# Pmaster-A9112-HOST_0.net
KiCad netlist of a schematic drawn in Altium Designer
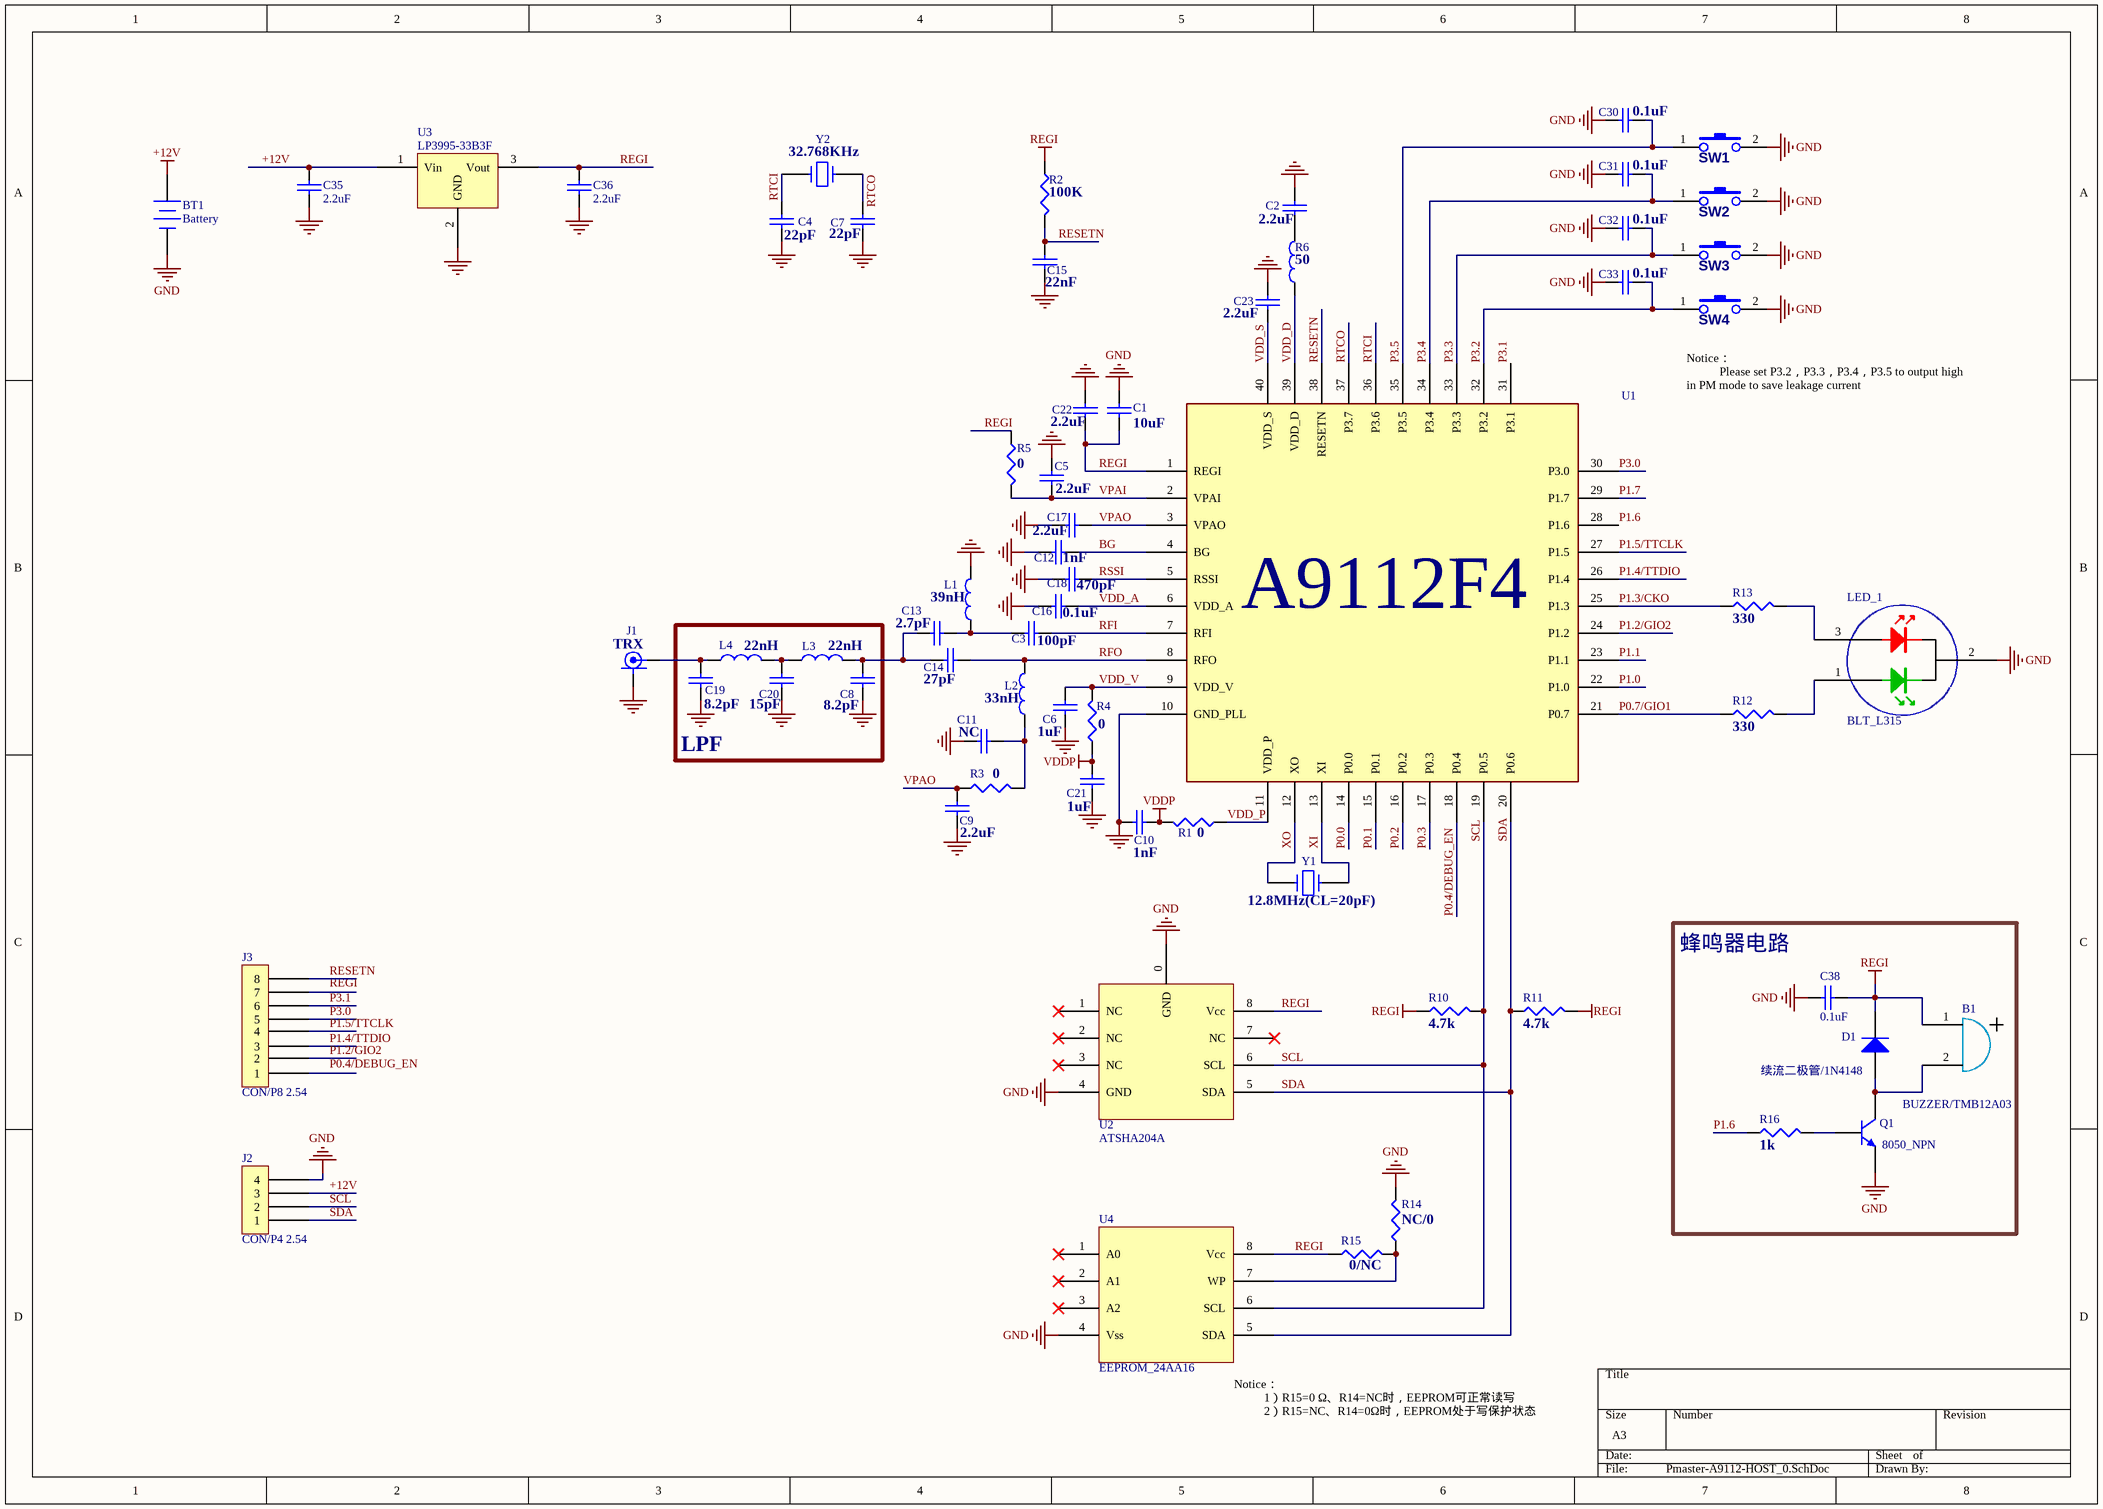
[diagram p0: Pmaster-A9112-HOST_0.SchDoc]

(export (version "E")
  (design (tool "Eeschema 10.0.6"))
  (components
    (comp (ref "B1")
      (value "BUZZER/TMB12A03")
      (footprint "BUZEER")
      (libsource (lib "my-amiccom") (part "BUZZER"))
    )
    (comp (ref "BT1")
      (value "Battery")
      (footprint "BAT-2")
      (description "Multicell Battery")
      (fields (field (name "PUBLISHER") "Altium Limited"))
      (libsource (lib "Miscellaneous Devices") (part "Battery"))
    )
    (comp (ref "C1") (value "10uF") (footprint "1206") (libsource (lib "*") (part "CAP")))
    (comp (ref "C2") (value "2.2uF") (footprint "0603") (libsource (lib "*") (part "CAP")))
    (comp (ref "C3") (value "100pF") (footprint "0402") (libsource (lib "*") (part "CAP")))
    (comp (ref "C4")
      (value "22pF")
      (footprint "0402")
      (description "Chip C")
      (libsource (lib "*") (part "C/0402"))
    )
    (comp (ref "C5") (value "2.2uF") (footprint "0603") (libsource (lib "*") (part "CAP")))
    (comp (ref "C6") (value "1uF") (footprint "0603") (libsource (lib "*") (part "CAP")))
    (comp (ref "C7")
      (value "22pF")
      (footprint "0402")
      (description "Chip C")
      (libsource (lib "*") (part "C/0402"))
    )
    (comp (ref "C8") (value "8.2pF") (footprint "0402") (libsource (lib "*") (part "CAP")))
    (comp (ref "C9")
      (value "2.2uF")
      (footprint "0603")
      (description "Chip C")
      (libsource (lib "*") (part "C/0603"))
    )
    (comp (ref "C10") (value "1nF") (footprint "0402") (libsource (lib "*") (part "CAP")))
    (comp (ref "C11")
      (value "NC")
      (footprint "0402")
      (description "Chip C")
      (libsource (lib "*") (part "C/0603"))
    )
    (comp (ref "C12") (value "1nF") (footprint "0402") (libsource (lib "*") (part "CAP")))
    (comp (ref "C13") (value "2.7pF") (footprint "0402") (libsource (lib "*") (part "CAP")))
    (comp (ref "C14") (value "27pF") (footprint "0402") (libsource (lib "*") (part "CAP")))
    (comp (ref "C15")
      (value "22nF")
      (footprint "0402")
      (description "Chip C")
      (libsource (lib "*") (part "C/1206"))
    )
    (comp (ref "C16") (value "0.1uF") (footprint "0603") (libsource (lib "*") (part "CAP")))
    (comp (ref "C17")
      (value "2.2uF")
      (footprint "0603")
      (description "Chip C")
      (libsource (lib "*") (part "C/0603"))
    )
    (comp (ref "C18") (value "470pF") (footprint "0402") (libsource (lib "*") (part "CAP")))
    (comp (ref "C19")
      (value "8.2pF")
      (footprint "0402")
      (description "Chip C")
      (libsource (lib "*") (part "C/0603"))
    )
    (comp (ref "C20")
      (value "15pF")
      (footprint "0402")
      (description "Chip C")
      (libsource (lib "*") (part "C/0603"))
    )
    (comp (ref "C21") (value "1uF") (footprint "0402") (libsource (lib "*") (part "CAP")))
    (comp (ref "C22") (value "2.2uF") (footprint "0603") (libsource (lib "*") (part "CAP")))
    (comp (ref "C23") (value "2.2uF") (footprint "0603") (libsource (lib "*") (part "CAP")))
    (comp (ref "C30") (value "0.1uF") (footprint "0603") (libsource (lib "*") (part "CAP")))
    (comp (ref "C31") (value "0.1uF") (footprint "0603") (libsource (lib "*") (part "CAP")))
    (comp (ref "C32") (value "0.1uF") (footprint "0603") (libsource (lib "*") (part "CAP")))
    (comp (ref "C33") (value "0.1uF") (footprint "0603") (libsource (lib "*") (part "CAP")))
    (comp (ref "C35") (value "2.2uF") (footprint "0603") (libsource (lib "") (part "CAP_1")))
    (comp (ref "C36")
      (value "2.2uF")
      (footprint "0603")
      (description "Chip C")
      (libsource (lib "*") (part "C/0603"))
    )
    (comp (ref "C38")
      (value "0.1uF")
      (footprint "A0402")
      (description "Chip C")
      (libsource (lib "*") (part "C/0603"))
    )
    (comp (ref "D1")
      (value "续流二极管/1N4148")
      (footprint "0805")
      (description "Default Diode")
      (fields (field (name "PUBLISHER") "Altium Limited"))
      (libsource (lib "Miscellaneous Devices") (part "Diode"))
    )
    (comp (ref "J1") (value "TRX") (footprint "SMA CONNECTOR") (libsource (lib "*") (part "SMA CONNECTOR")))
    (comp (ref "J2")
      (value "CON/P4 2.54")
      (footprint "HDR4_2.54")
      (libsource (lib "my-amiccom") (part "CON/P4 2.54"))
    )
    (comp (ref "J3")
      (value "CON/P8 2.54")
      (footprint "HDR8_2.54")
      (libsource (lib "my-amiccom") (part "CON/P8 2.54"))
    )
    (comp (ref "L1")
      (value "39nH")
      (footprint "0402")
      (description "Chip L")
      (libsource (lib "*") (part "L/0402"))
    )
    (comp (ref "L2")
      (value "33nH")
      (footprint "0402")
      (description "Chip L")
      (libsource (lib "*") (part "L/0402"))
    )
    (comp (ref "L3") (value "22nH") (footprint "0402") (libsource (lib "*") (part "L/0603")))
    (comp (ref "L4") (value "22nH") (footprint "0402") (libsource (lib "*") (part "L/0603")))
    (comp (ref "LED_1")
      (value "BLT_L315")
      (footprint "LED_BI-COLOR")
      (libsource (lib "my-amiccom") (part "double_LED"))
    )
    (comp (ref "Q1")
      (value "8050_NPN")
      (footprint "SOT23_N")
      (description "NPN Bipolar Transistor")
      (fields (field (name "PUBLISHER") "Altium Limited"))
      (libsource (lib "Miscellaneous Devices") (part "NPN"))
    )
    (comp (ref "R1") (value "0") (footprint "0402") (libsource (lib "*") (part "RES1")))
    (comp (ref "R2")
      (value "100K")
      (footprint "0402")
      (description "Chip R")
      (libsource (lib "*") (part "R/0402"))
    )
    (comp (ref "R3")
      (value "0")
      (footprint "0402")
      (description "Chip  R")
      (libsource (lib "*") (part "R/0603"))
    )
    (comp (ref "R4")
      (value "0")
      (footprint "0402")
      (description "Chip  R")
      (libsource (lib "*") (part "R/0603"))
    )
    (comp (ref "R5") (value "0") (footprint "0402") (libsource (lib "*") (part "RES1")))
    (comp (ref "R6") (value "50") (footprint "0402") (libsource (lib "") (part "L/0603_1")))
    (comp (ref "R10") (value "4.7k") (footprint "0402") (libsource (lib "*") (part "RES1")))
    (comp (ref "R11") (value "4.7k") (footprint "0402") (libsource (lib "*") (part "RES1")))
    (comp (ref "R12") (value "330") (footprint "0402") (libsource (lib "*") (part "RES1")))
    (comp (ref "R13") (value "330") (footprint "0402") (libsource (lib "*") (part "RES1")))
    (comp (ref "R14") (value "NC/0") (footprint "0402") (libsource (lib "*") (part "RES1")))
    (comp (ref "R15") (value "0/NC") (footprint "0402") (libsource (lib "*") (part "RES1")))
    (comp (ref "R16") (value "1k") (footprint "0402") (libsource (lib "*") (part "RES1")))
    (comp (ref "SW1")
      (value "SW-P~{B}2P")
      (footprint "SW4P")
      (libsource (lib "my-amiccom") (part "SW-PB{backslash}2P"))
    )
    (comp (ref "SW2")
      (value "SW-P~{B}2P")
      (footprint "SW4P")
      (libsource (lib "my-amiccom") (part "SW-PB{backslash}2P"))
    )
    (comp (ref "SW3")
      (value "SW-P~{B}2P")
      (footprint "SW4P")
      (libsource (lib "my-amiccom") (part "SW-PB{backslash}2P"))
    )
    (comp (ref "SW4")
      (value "SW-P~{B}2P")
      (footprint "SW4P")
      (libsource (lib "my-amiccom") (part "SW-PB{backslash}2P"))
    )
    (comp (ref "U1") (value "A9112F4") (footprint "QFN40_5*5") (libsource (lib "AMICCOM-S") (part "A9112F4")))
    (comp (ref "U2")
      (value "ATSHA204A")
      (footprint "UDFN_8P")
      (libsource (lib "my-amiccom") (part "ATSHA204A"))
    )
    (comp (ref "U3")
      (value "LP3995-33B3F")
      (footprint "SOT-23_N")
      (description "GMT 3.3V REGULTOR")
      (libsource (lib "*") (part "REG{backslash}G903{backslash}3.3V{backslash}SOT-223"))
    )
    (comp (ref "U4")
      (value "EEPROM_24AA16")
      (footprint "MSOP-MS8_N")
      (libsource (lib "my-amiccom") (part "EEPROM_24AA16"))
    )
    (comp (ref "Y1")
      (value "12.8MHz(CL=20pF)")
      (footprint "XTAL1")
      (description "Crystal")
      (libsource (lib "*") (part "CRYSTAL"))
    )
    (comp (ref "Y2")
      (value "32.768KHz")
      (footprint "XTAL_3215")
      (description "Crystal")
      (libsource (lib "*") (part "CRYSTAL"))
    )
  )
  (nets
    (net (code "1") (name "+12V") (class "Default")
      (node (ref "BT1") (pin "1") (pinfunction "+_1") (pintype "passive"))
      (node (ref "C35") (pin "2") (pinfunction "2_2") (pintype "passive"))
      (node (ref "J2") (pin "3") (pinfunction "3_3") (pintype "power_in"))
      (node (ref "U3") (pin "1") (pinfunction "Vin_1") (pintype "passive"))
    )
    (net (code "2") (name "/BG") (class "Default")
      (node (ref "C12") (pin "1") (pinfunction "1_1") (pintype "passive"))
      (node (ref "U1") (pin "4") (pinfunction "BG_4") (pintype "passive"))
    )
    (net (code "3") (name "/P0.0") (class "Default")
      (node (ref "U1") (pin "14") (pinfunction "P0.0_14") (pintype "passive"))
    )
    (net (code "4") (name "/P0.1") (class "Default")
      (node (ref "U1") (pin "15") (pinfunction "P0.1_15") (pintype "passive"))
    )
    (net (code "5") (name "/P0.2") (class "Default")
      (node (ref "U1") (pin "16") (pinfunction "P0.2_16") (pintype "passive"))
    )
    (net (code "6") (name "/P0.3") (class "Default")
      (node (ref "U1") (pin "17") (pinfunction "P0.3_17") (pintype "passive"))
    )
    (net (code "7") (name "/P0.4{slash}DEBUG_EN") (class "Default")
      (node (ref "U1") (pin "18") (pinfunction "P0.4_18") (pintype "passive"))
    )
    (net (code "8") (name "/P0.7{slash}GIO1") (class "Default")
      (node (ref "R12") (pin "1") (pinfunction "1_1") (pintype "passive"))
      (node (ref "U1") (pin "21") (pinfunction "P0.7_21") (pintype "passive"))
    )
    (net (code "9") (name "/P1.0") (class "Default")
      (node (ref "U1") (pin "22") (pinfunction "P1.0_22") (pintype "passive"))
    )
    (net (code "10") (name "/P1.1") (class "Default")
      (node (ref "U1") (pin "23") (pinfunction "P1.1_23") (pintype "passive"))
    )
    (net (code "11") (name "/P1.2{slash}GIO2") (class "Default")
      (node (ref "J3") (pin "2") (pinfunction "2_2") (pintype "power_in"))
      (node (ref "U1") (pin "24") (pinfunction "P1.2_24") (pintype "passive"))
    )
    (net (code "12") (name "/P1.3{slash}CKO") (class "Default")
      (node (ref "R13") (pin "1") (pinfunction "1_1") (pintype "passive"))
      (node (ref "U1") (pin "25") (pinfunction "P1.3_25") (pintype "passive"))
    )
    (net (code "13") (name "/P1.4{slash}TTDIO") (class "Default")
      (node (ref "J3") (pin "3") (pinfunction "3_3") (pintype "power_in"))
      (node (ref "U1") (pin "26") (pinfunction "P1.4_26") (pintype "passive"))
    )
    (net (code "14") (name "/P1.5{slash}TTCLK") (class "Default")
      (node (ref "J3") (pin "4") (pinfunction "4_4") (pintype "power_in"))
      (node (ref "U1") (pin "27") (pinfunction "P1.5_27") (pintype "passive"))
    )
    (net (code "15") (name "/P1.6") (class "Default")
      (node (ref "R16") (pin "1") (pinfunction "1_1") (pintype "passive"))
      (node (ref "U1") (pin "28") (pinfunction "P1.6_28") (pintype "passive"))
    )
    (net (code "16") (name "/P1.7") (class "Default")
      (node (ref "U1") (pin "29") (pinfunction "P1.7_29") (pintype "passive"))
    )
    (net (code "17") (name "/P3.0") (class "Default")
      (node (ref "J3") (pin "5") (pinfunction "5_5") (pintype "power_in"))
      (node (ref "U1") (pin "30") (pinfunction "P3.0_30") (pintype "passive"))
    )
    (net (code "18") (name "/P3.1") (class "Default")
      (node (ref "J3") (pin "6") (pinfunction "6_6") (pintype "power_in"))
      (node (ref "U1") (pin "31") (pinfunction "P3.1_31") (pintype "passive"))
    )
    (net (code "19") (name "/P3.2") (class "Default")
      (node (ref "C33") (pin "2") (pinfunction "2_2") (pintype "passive"))
      (node (ref "SW4") (pin "1") (pinfunction "1_1") (pintype "passive"))
      (node (ref "U1") (pin "32") (pinfunction "P3.2_32") (pintype "passive"))
    )
    (net (code "20") (name "/P3.3") (class "Default")
      (node (ref "C32") (pin "2") (pinfunction "2_2") (pintype "passive"))
      (node (ref "SW3") (pin "1") (pinfunction "1_1") (pintype "passive"))
      (node (ref "U1") (pin "33") (pinfunction "P3.3_33") (pintype "passive"))
    )
    (net (code "21") (name "/P3.4") (class "Default")
      (node (ref "C31") (pin "2") (pinfunction "2_2") (pintype "passive"))
      (node (ref "SW2") (pin "1") (pinfunction "1_1") (pintype "passive"))
      (node (ref "U1") (pin "34") (pinfunction "P3.4_34") (pintype "passive"))
    )
    (net (code "22") (name "/P3.5") (class "Default")
      (node (ref "C30") (pin "2") (pinfunction "2_2") (pintype "passive"))
      (node (ref "SW1") (pin "1") (pinfunction "1_1") (pintype "passive"))
      (node (ref "U1") (pin "35") (pinfunction "P3.5_35") (pintype "passive"))
    )
    (net (code "23") (name "/RESETN") (class "Default")
      (node (ref "C15") (pin "1") (pinfunction "1_1") (pintype "passive"))
      (node (ref "J3") (pin "8") (pinfunction "8_8") (pintype "power_in"))
      (node (ref "R2") (pin "2") (pinfunction "2_2") (pintype "passive"))
      (node (ref "U1") (pin "38") (pinfunction "RESETN_38") (pintype "passive"))
    )
    (net (code "24") (name "/RFI") (class "Default")
      (node (ref "C3") (pin "1") (pinfunction "1_1") (pintype "passive"))
      (node (ref "U1") (pin "7") (pinfunction "RFI_7") (pintype "passive"))
    )
    (net (code "25") (name "/RFO") (class "Default")
      (node (ref "C14") (pin "1") (pinfunction "1_1") (pintype "passive"))
      (node (ref "L2") (pin "2") (pinfunction "2_2") (pintype "passive"))
      (node (ref "U1") (pin "8") (pinfunction "RFO_8") (pintype "passive"))
    )
    (net (code "26") (name "/RSSI") (class "Default")
      (node (ref "C18") (pin "2") (pinfunction "2_2") (pintype "passive"))
      (node (ref "U1") (pin "5") (pinfunction "RSSI_5") (pintype "passive"))
    )
    (net (code "27") (name "/RTCI") (class "Default")
      (node (ref "C4") (pin "1") (pinfunction "1_1") (pintype "passive"))
      (node (ref "U1") (pin "36") (pinfunction "P3.6_36") (pintype "passive"))
      (node (ref "Y2") (pin "1") (pinfunction "1_1") (pintype "passive"))
    )
    (net (code "28") (name "/RTCO") (class "Default")
      (node (ref "C7") (pin "1") (pinfunction "1_1") (pintype "passive"))
      (node (ref "U1") (pin "37") (pinfunction "P3.7_37") (pintype "passive"))
      (node (ref "Y2") (pin "2") (pinfunction "2_2") (pintype "passive"))
    )
    (net (code "29") (name "/SCL") (class "Default")
      (node (ref "J2") (pin "2") (pinfunction "2_2") (pintype "power_in"))
      (node (ref "R10") (pin "2") (pinfunction "2_2") (pintype "passive"))
      (node (ref "U1") (pin "19") (pinfunction "P0.5_19") (pintype "passive"))
      (node (ref "U2") (pin "6") (pinfunction "SCL_6") (pintype "passive"))
      (node (ref "U4") (pin "6") (pinfunction "SCL_6") (pintype "passive"))
    )
    (net (code "30") (name "/SDA") (class "Default")
      (node (ref "J2") (pin "1") (pinfunction "1_1") (pintype "power_in"))
      (node (ref "R11") (pin "1") (pinfunction "1_1") (pintype "passive"))
      (node (ref "U1") (pin "20") (pinfunction "P0.6_20") (pintype "passive"))
      (node (ref "U2") (pin "5") (pinfunction "SDA_5") (pintype "passive"))
      (node (ref "U4") (pin "5") (pinfunction "SDA_5") (pintype "passive"))
    )
    (net (code "31") (name "/VDD_A") (class "Default")
      (node (ref "C16") (pin "2") (pinfunction "2_2") (pintype "passive"))
      (node (ref "U1") (pin "6") (pinfunction "VDD_A_6") (pintype "passive"))
    )
    (net (code "32") (name "/VDD_D") (class "Default")
      (node (ref "R6") (pin "1") (pinfunction "1_1") (pintype "passive"))
      (node (ref "U1") (pin "39") (pinfunction "VDD_D_39") (pintype "passive"))
    )
    (net (code "33") (name "/VDD_P") (class "Default")
      (node (ref "R1") (pin "1") (pinfunction "1_1") (pintype "passive"))
      (node (ref "U1") (pin "11") (pinfunction "VDD_P_11") (pintype "passive"))
    )
    (net (code "35") (name "/VDD_S") (class "Default")
      (node (ref "C23") (pin "2") (pinfunction "2_2") (pintype "passive"))
      (node (ref "U1") (pin "40") (pinfunction "VDD_S_40") (pintype "passive"))
    )
    (net (code "36") (name "/VDD_V") (class "Default")
      (node (ref "C6") (pin "1") (pinfunction "1_1") (pintype "passive"))
      (node (ref "R4") (pin "2") (pinfunction "2_2") (pintype "passive"))
      (node (ref "U1") (pin "9") (pinfunction "VDD_V_9") (pintype "passive"))
    )
    (net (code "37") (name "/VPAI") (class "Default")
      (node (ref "C5") (pin "1") (pinfunction "1_1") (pintype "passive"))
      (node (ref "R5") (pin "2") (pinfunction "2_2") (pintype "passive"))
      (node (ref "U1") (pin "2") (pinfunction "VPAI_2") (pintype "passive"))
    )
    (net (code "38") (name "/VPAO") (class "Default")
      (node (ref "C17") (pin "1") (pinfunction "1_1") (pintype "passive"))
      (node (ref "C9") (pin "1") (pinfunction "1_1") (pintype "passive"))
      (node (ref "R3") (pin "1") (pinfunction "1_1") (pintype "passive"))
      (node (ref "U1") (pin "3") (pinfunction "VPAO_3") (pintype "passive"))
    )
    (net (code "39") (name "/XI") (class "Default")
      (node (ref "U1") (pin "13") (pinfunction "XI_13") (pintype "passive"))
      (node (ref "Y1") (pin "1") (pinfunction "1_1") (pintype "passive"))
    )
    (net (code "40") (name "/XO") (class "Default")
      (node (ref "U1") (pin "12") (pinfunction "XO_12") (pintype "passive"))
      (node (ref "Y1") (pin "2") (pinfunction "2_2") (pintype "passive"))
    )
    (net (code "41") (name "GND") (class "Default")
      (node (ref "BT1") (pin "2") (pinfunction "-_2") (pintype "passive"))
      (node (ref "C1") (pin "2") (pinfunction "2_2") (pintype "passive"))
      (node (ref "C10") (pin "1") (pinfunction "1_1") (pintype "passive"))
      (node (ref "C11") (pin "1") (pinfunction "1_1") (pintype "passive"))
      (node (ref "C12") (pin "2") (pinfunction "2_2") (pintype "passive"))
      (node (ref "C15") (pin "2") (pinfunction "2_2") (pintype "passive"))
      (node (ref "C16") (pin "1") (pinfunction "1_1") (pintype "passive"))
      (node (ref "C17") (pin "2") (pinfunction "2_2") (pintype "passive"))
      (node (ref "C18") (pin "1") (pinfunction "1_1") (pintype "passive"))
      (node (ref "C19") (pin "2") (pinfunction "2_2") (pintype "passive"))
      (node (ref "C2") (pin "1") (pinfunction "1_1") (pintype "passive"))
      (node (ref "C20") (pin "2") (pinfunction "2_2") (pintype "passive"))
      (node (ref "C21") (pin "1") (pinfunction "1_1") (pintype "passive"))
      (node (ref "C22") (pin "1") (pinfunction "1_1") (pintype "passive"))
      (node (ref "C23") (pin "1") (pinfunction "1_1") (pintype "passive"))
      (node (ref "C30") (pin "1") (pinfunction "1_1") (pintype "passive"))
      (node (ref "C31") (pin "1") (pinfunction "1_1") (pintype "passive"))
      (node (ref "C32") (pin "1") (pinfunction "1_1") (pintype "passive"))
      (node (ref "C33") (pin "1") (pinfunction "1_1") (pintype "passive"))
      (node (ref "C35") (pin "1") (pinfunction "1_1") (pintype "passive"))
      (node (ref "C36") (pin "2") (pinfunction "2_2") (pintype "passive"))
      (node (ref "C38") (pin "1") (pinfunction "1_1") (pintype "passive"))
      (node (ref "C4") (pin "2") (pinfunction "2_2") (pintype "passive"))
      (node (ref "C5") (pin "2") (pinfunction "2_2") (pintype "passive"))
      (node (ref "C7") (pin "2") (pinfunction "2_2") (pintype "passive"))
      (node (ref "C8") (pin "1") (pinfunction "1_1") (pintype "passive"))
      (node (ref "C9") (pin "2") (pinfunction "2_2") (pintype "passive"))
      (node (ref "J1") (pin "0") (pinfunction "SHIELD_0") (pintype "passive"))
      (node (ref "J2") (pin "4") (pinfunction "4_4") (pintype "power_in"))
      (node (ref "L1") (pin "2") (pinfunction "2_2") (pintype "passive"))
      (node (ref "LED_1") (pin "2") (pintype "passive"))
      (node (ref "Q1") (pin "3") (pinfunction "E_3") (pintype "passive"))
      (node (ref "R14") (pin "2") (pinfunction "2_2") (pintype "passive"))
      (node (ref "SW1") (pin "2") (pinfunction "2_2") (pintype "passive"))
      (node (ref "SW2") (pin "2") (pinfunction "2_2") (pintype "passive"))
      (node (ref "SW3") (pin "2") (pinfunction "2_2") (pintype "passive"))
      (node (ref "SW4") (pin "2") (pinfunction "2_2") (pintype "passive"))
      (node (ref "U1") (pin "10") (pinfunction "GND_PLL_10") (pintype "passive"))
      (node (ref "U2") (pin "0") (pinfunction "GND_0") (pintype "passive"))
      (node (ref "U2") (pin "4") (pinfunction "GND_4") (pintype "passive"))
      (node (ref "U3") (pin "2") (pinfunction "GND_2") (pintype "passive"))
      (node (ref "U4") (pin "4") (pinfunction "Vss_4") (pintype "passive"))
    )
    (net (code "42") (name "Net-(C2-Pad2)") (class "Default")
      (node (ref "C2") (pin "2") (pinfunction "2_2") (pintype "passive"))
      (node (ref "R6") (pin "2") (pinfunction "2_2") (pintype "passive"))
    )
    (net (code "43") (name "Net-(C11-Pad2)") (class "Default")
      (node (ref "C11") (pin "2") (pinfunction "2_2") (pintype "passive"))
      (node (ref "L2") (pin "1") (pinfunction "1_1") (pintype "passive"))
      (node (ref "R3") (pin "2") (pinfunction "2_2") (pintype "passive"))
    )
    (net (code "44") (name "Net-(C13-Pad1)") (class "Default")
      (node (ref "C13") (pin "1") (pinfunction "1_1") (pintype "passive"))
      (node (ref "C3") (pin "2") (pinfunction "2_2") (pintype "passive"))
      (node (ref "L1") (pin "1") (pinfunction "1_1") (pintype "passive"))
    )
    (net (code "45") (name "Net-(C13-Pad2)") (class "Default")
      (node (ref "C13") (pin "2") (pinfunction "2_2") (pintype "passive"))
      (node (ref "C14") (pin "2") (pinfunction "2_2") (pintype "passive"))
      (node (ref "C8") (pin "2") (pinfunction "2_2") (pintype "passive"))
      (node (ref "L3") (pin "2") (pinfunction "2_2") (pintype "passive"))
    )
    (net (code "46") (name "Net-(C20-Pad1)") (class "Default")
      (node (ref "C20") (pin "1") (pinfunction "1_1") (pintype "passive"))
      (node (ref "L3") (pin "1") (pinfunction "1_1") (pintype "passive"))
      (node (ref "L4") (pin "2") (pinfunction "2_2") (pintype "passive"))
    )
    (net (code "47") (name "Net-(D1-A)") (class "Default")
      (node (ref "B1") (pin "2") (pintype "passive"))
      (node (ref "D1") (pin "1") (pinfunction "A_1") (pintype "passive"))
      (node (ref "Q1") (pin "1") (pinfunction "C_1") (pintype "passive"))
    )
    (net (code "48") (name "Net-(J1-CENTER_1)") (class "Default")
      (node (ref "C19") (pin "1") (pinfunction "1_1") (pintype "passive"))
      (node (ref "J1") (pin "1") (pinfunction "CENTER_1_1") (pintype "passive"))
      (node (ref "L4") (pin "1") (pinfunction "1_1") (pintype "passive"))
    )
    (net (code "49") (name "Net-(LED_1-9)") (class "Default")
      (node (ref "LED_1") (pin "1") (pinfunction "9_1") (pintype "passive"))
      (node (ref "R12") (pin "2") (pinfunction "2_2") (pintype "passive"))
    )
    (net (code "50") (name "Net-(LED_1-RED)") (class "Default")
      (node (ref "LED_1") (pin "3") (pinfunction "RED_3") (pintype "passive"))
      (node (ref "R13") (pin "2") (pinfunction "2_2") (pintype "passive"))
    )
    (net (code "51") (name "Net-(Q1-B)") (class "Default")
      (node (ref "Q1") (pin "2") (pinfunction "B_2") (pintype "passive"))
      (node (ref "R16") (pin "2") (pinfunction "2_2") (pintype "passive"))
    )
    (net (code "52") (name "Net-(U4-WP)") (class "Default")
      (node (ref "R14") (pin "1") (pinfunction "1_1") (pintype "passive"))
      (node (ref "R15") (pin "2") (pinfunction "2_2") (pintype "passive"))
      (node (ref "U4") (pin "7") (pinfunction "WP_7") (pintype "passive"))
    )
    (net (code "53") (name "REGI") (class "Default")
      (node (ref "B1") (pin "1") (pintype "passive"))
      (node (ref "C1") (pin "1") (pinfunction "1_1") (pintype "passive"))
      (node (ref "C22") (pin "2") (pinfunction "2_2") (pintype "passive"))
      (node (ref "C36") (pin "1") (pinfunction "1_1") (pintype "passive"))
      (node (ref "C38") (pin "2") (pinfunction "2_2") (pintype "passive"))
      (node (ref "D1") (pin "2") (pinfunction "K_2") (pintype "passive"))
      (node (ref "R10") (pin "1") (pinfunction "1_1") (pintype "passive"))
      (node (ref "R11") (pin "2") (pinfunction "2_2") (pintype "passive"))
      (node (ref "R15") (pin "1") (pinfunction "1_1") (pintype "passive"))
      (node (ref "R2") (pin "1") (pinfunction "1_1") (pintype "passive"))
      (node (ref "R5") (pin "1") (pinfunction "1_1") (pintype "passive"))
      (node (ref "U1") (pin "1") (pinfunction "REGI_1") (pintype "passive"))
      (node (ref "U2") (pin "8") (pinfunction "Vcc_8") (pintype "passive"))
      (node (ref "U3") (pin "3") (pinfunction "Vout_3") (pintype "passive"))
      (node (ref "U4") (pin "8") (pinfunction "Vcc_8") (pintype "passive"))
    )
    (net (code "54") (name "VCO_GND") (class "Default")
      (node (ref "C6") (pin "2") (pinfunction "2_2") (pintype "passive"))
    )
    (net (code "55") (name "VDDP") (class "Default")
      (node (ref "C10") (pin "2") (pinfunction "2_2") (pintype "passive"))
      (node (ref "C21") (pin "2") (pinfunction "2_2") (pintype "passive"))
      (node (ref "R1") (pin "2") (pinfunction "2_2") (pintype "passive"))
      (node (ref "R4") (pin "1") (pinfunction "1_1") (pintype "passive"))
    )
    (net (code "56") (name "unconnected-(J3-Pad1)") (class "Default")
      (node (ref "J3") (pin "1") (pinfunction "1_1") (pintype "power_in"))
    )
    (net (code "57") (name "unconnected-(J3-Pad7)") (class "Default")
      (node (ref "J3") (pin "7") (pinfunction "7_7") (pintype "power_in"))
    )
    (net (code "58") (name "unconnected-(U2-NC-Pad1)") (class "Default")
      (node (ref "U2") (pin "1") (pinfunction "NC_1") (pintype "passive+no_connect"))
    )
    (net (code "59") (name "unconnected-(U2-NC-Pad2)") (class "Default")
      (node (ref "U2") (pin "2") (pinfunction "NC_2") (pintype "passive+no_connect"))
    )
    (net (code "60") (name "unconnected-(U2-NC-Pad3)") (class "Default")
      (node (ref "U2") (pin "3") (pinfunction "NC_3") (pintype "passive+no_connect"))
    )
    (net (code "61") (name "unconnected-(U2-NC-Pad7)") (class "Default")
      (node (ref "U2") (pin "7") (pinfunction "NC_7") (pintype "passive+no_connect"))
    )
    (net (code "62") (name "unconnected-(U4-A0-Pad1)") (class "Default")
      (node (ref "U4") (pin "1") (pinfunction "A0_1") (pintype "passive+no_connect"))
    )
    (net (code "63") (name "unconnected-(U4-A1-Pad2)") (class "Default")
      (node (ref "U4") (pin "2") (pinfunction "A1_2") (pintype "passive+no_connect"))
    )
    (net (code "64") (name "unconnected-(U4-A2-Pad3)") (class "Default")
      (node (ref "U4") (pin "3") (pinfunction "A2_3") (pintype "passive+no_connect"))
    )
  )
)
